# display_prog.net
KiCad netlist of a schematic drawn in EAGLE
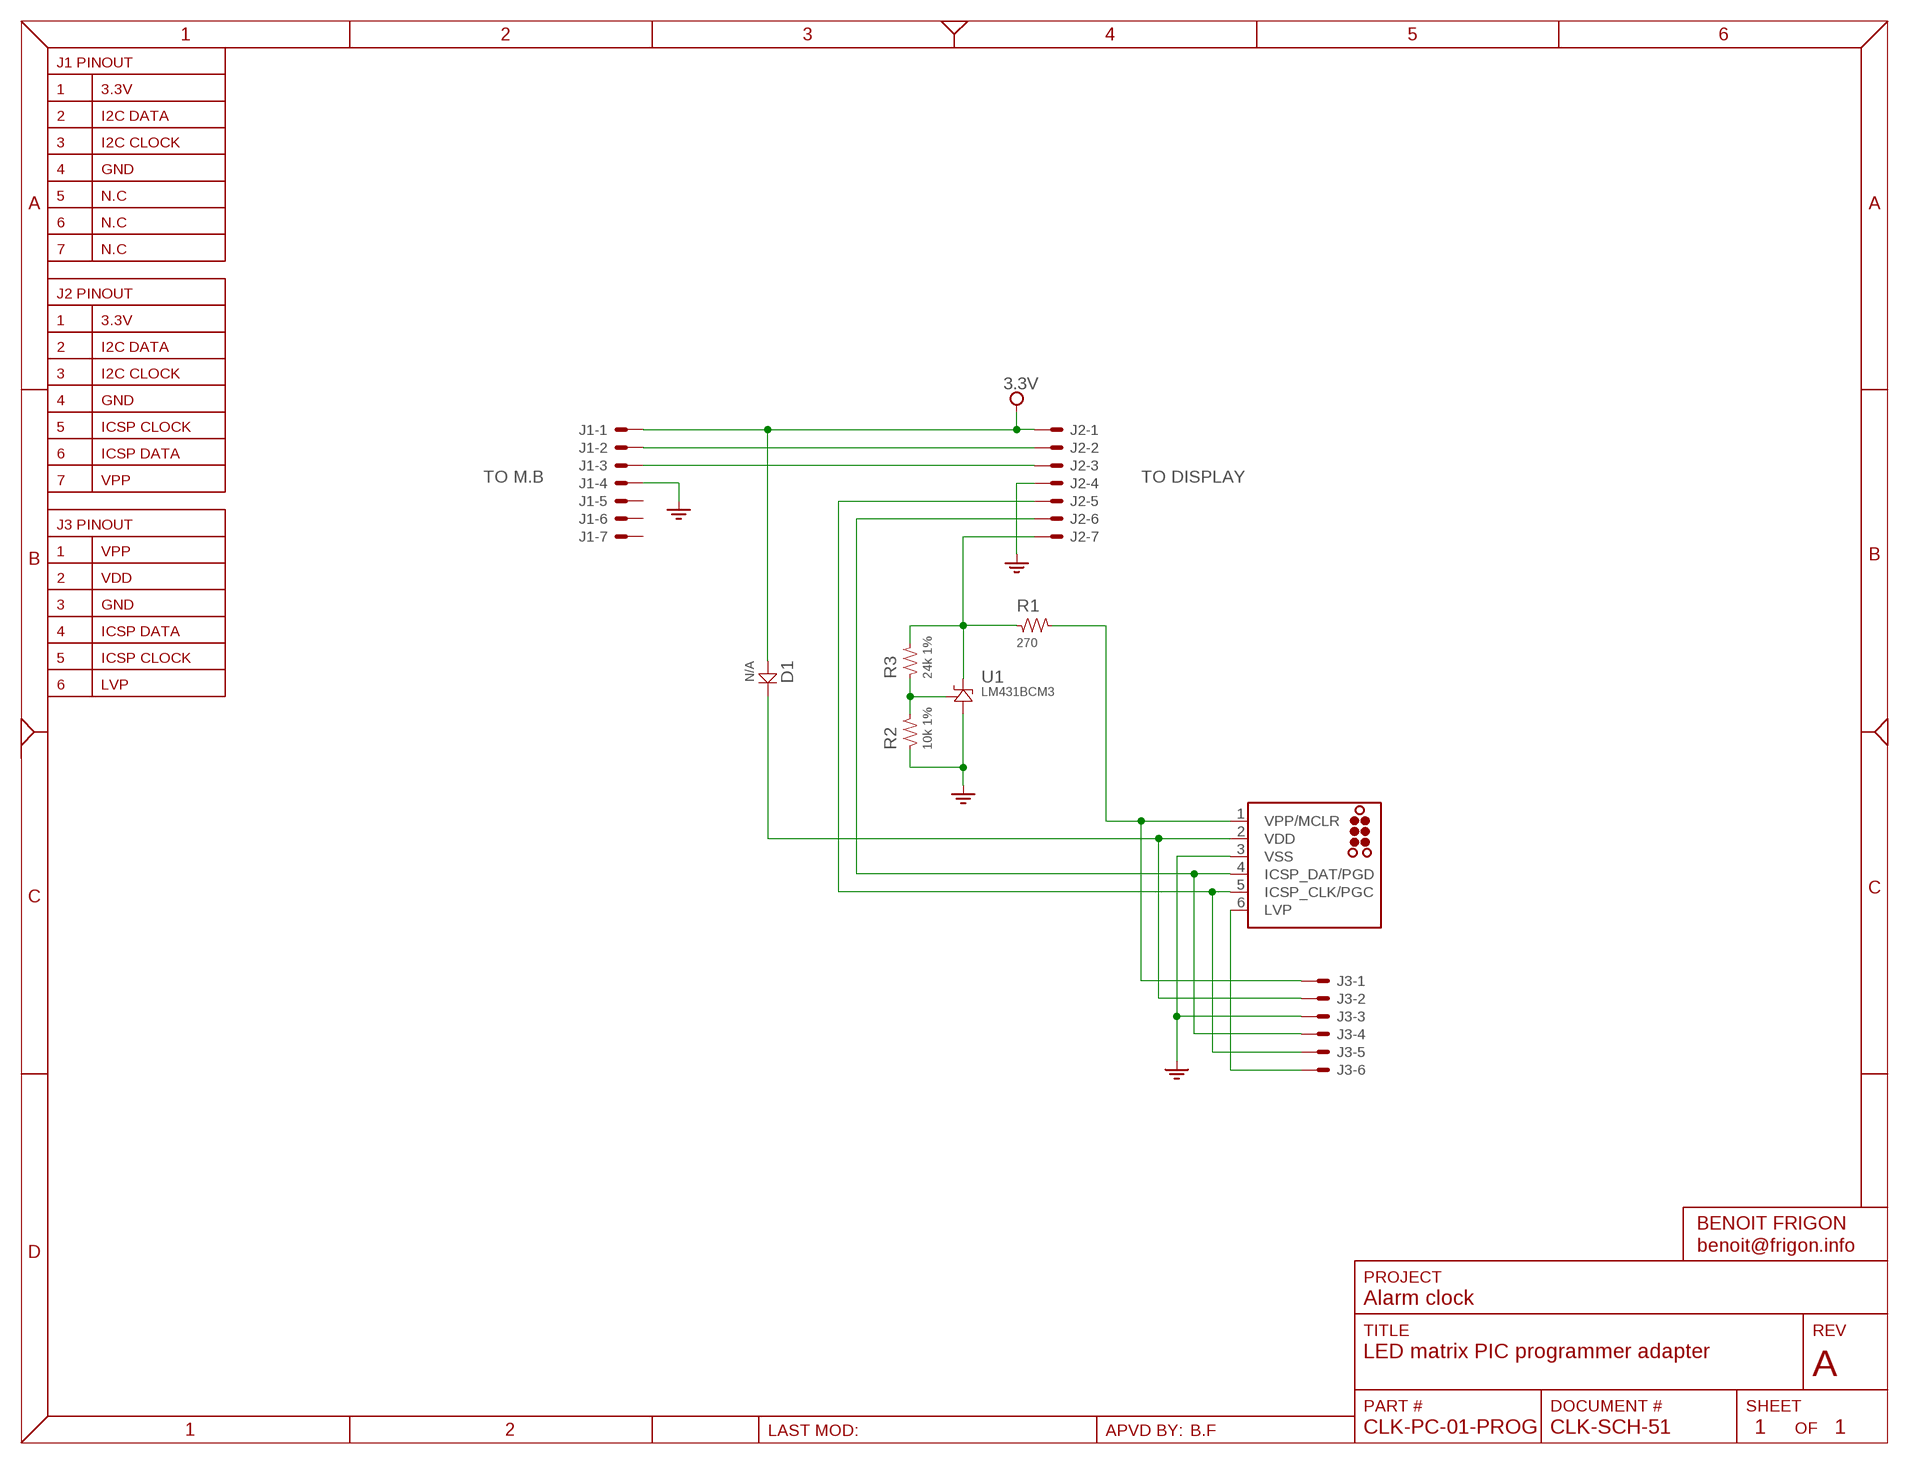
[diagram p0: schematic, sheet 1]

(export (version "E")
  (design (tool "Eeschema 10.0.6"))
  (components
    (comp (ref "D1")
      (value "N/A")
      (footprint "eagle-import:DIODE_0603")
      (libsource (lib "eagle-import") (part "DIODE-0603"))
    )
    (comp (ref "J1")
      (value "SNG-2MM-HEADER-07-V")
      (footprint "eagle-import:DF3X-7P-2DSA")
      (description "{DESCRIPTION} - SMT Vertical")
      (fields
        (field (name "MFG") "Hirose Electronic")
        (field (name "MFG_1") "Hirose Electronic")
        (field (name "SKU") "DF3X-7P-2DSA")
      )
      (libsource (lib "eagle-import") (part "SNG-2MM-HEADER-07-V"))
    )
    (comp (ref "J2")
      (value "SNG-2MM-HEADER-07-V")
      (footprint "eagle-import:DF3X-7P-2DSA")
      (fields (field (name "MFG") "Hirose Electronic"))
      (libsource (lib "eagle-import") (part "SNG-2MM-HEADER-07-V"))
    )
    (comp (ref "J3")
      (value "SNG-100-HEADER-06-FL-V")
      (footprint "eagle-import:22-23-2061")
      (fields (field (name "MFG") "Molex"))
      (libsource (lib "eagle-import") (part "SNG-100-HEADER-06-FL-V"))
    )
    (comp (ref "J4")
      (value "TC2030-MCP")
      (footprint "eagle-import:TC2030-MCP")
      (fields (field (name "MFG") "Tag-Connect"))
      (libsource (lib "eagle-import") (part "TC2030-MCP"))
    )
    (comp (ref "R1")
      (value "270")
      (footprint "eagle-import:SMD_0603")
      (libsource (lib "eagle-import") (part "RES-0603"))
    )
    (comp (ref "R2")
      (value "10k 1%")
      (footprint "eagle-import:SMD_0603")
      (libsource (lib "eagle-import") (part "RES-0603"))
    )
    (comp (ref "R3")
      (value "24k 1%")
      (footprint "eagle-import:SMD_0603")
      (libsource (lib "eagle-import") (part "RES-0603"))
    )
    (comp (ref "U1")
      (value "LM431BCM3")
      (footprint "eagle-import:SOT23")
      (fields (field (name "MFG") "Texas Instruments"))
      (libsource (lib "eagle-import") (part "LM431?M3BC"))
    )
  )
  (nets
    (net (code "1") (name "3.3V") (class "Default")
      (node (ref "D1") (pin "A") (pinfunction "A_A") (pintype "passive"))
      (node (ref "J1") (pin "1") (pinfunction "S_1") (pintype "bidirectional"))
      (node (ref "J2") (pin "1") (pinfunction "S_1") (pintype "bidirectional"))
    )
    (net (code "2") (name "GND") (class "Default")
      (node (ref "J1") (pin "4") (pinfunction "S_4") (pintype "bidirectional"))
      (node (ref "J2") (pin "4") (pinfunction "S_4") (pintype "bidirectional"))
      (node (ref "J3") (pin "3") (pinfunction "S_3") (pintype "bidirectional"))
      (node (ref "J4") (pin "3") (pinfunction "VSS_3") (pintype "power_in"))
      (node (ref "R2") (pin "1") (pinfunction "1_1") (pintype "passive"))
      (node (ref "U1") (pin "3") (pinfunction "A_3") (pintype "passive"))
    )
    (net (code "3") (name "Net-(J1B-S)") (class "Default")
      (node (ref "J1") (pin "2") (pinfunction "S_2") (pintype "bidirectional"))
      (node (ref "J2") (pin "2") (pinfunction "S_2") (pintype "bidirectional"))
    )
    (net (code "4") (name "Net-(J1C-S)") (class "Default")
      (node (ref "J1") (pin "3") (pinfunction "S_3") (pintype "bidirectional"))
      (node (ref "J2") (pin "3") (pinfunction "S_3") (pintype "bidirectional"))
    )
    (net (code "5") (name "Net-(J2E-S)") (class "Default")
      (node (ref "J2") (pin "5") (pinfunction "S_5") (pintype "bidirectional"))
      (node (ref "J3") (pin "5") (pinfunction "S_5") (pintype "bidirectional"))
      (node (ref "J4") (pin "5") (pinfunction "ICSP_CLK/PGC_5") (pintype "output"))
    )
    (net (code "6") (name "Net-(J2F-S)") (class "Default")
      (node (ref "J2") (pin "6") (pinfunction "S_6") (pintype "bidirectional"))
      (node (ref "J3") (pin "4") (pinfunction "S_4") (pintype "bidirectional"))
      (node (ref "J4") (pin "4") (pinfunction "ICSP_DAT/PGD_4") (pintype "bidirectional"))
    )
    (net (code "7") (name "Net-(J2G-S)") (class "Default")
      (node (ref "J2") (pin "7") (pinfunction "S_7") (pintype "bidirectional"))
      (node (ref "R1") (pin "1") (pinfunction "1_1") (pintype "passive"))
      (node (ref "R3") (pin "2") (pinfunction "2_2") (pintype "passive"))
      (node (ref "U1") (pin "1") (pinfunction "K_1") (pintype "passive"))
    )
    (net (code "8") (name "Net-(J3A-S)") (class "Default")
      (node (ref "J3") (pin "1") (pinfunction "S_1") (pintype "bidirectional"))
      (node (ref "J4") (pin "1") (pinfunction "VPP/MCLR_1") (pintype "passive"))
      (node (ref "R1") (pin "2") (pinfunction "2_2") (pintype "passive"))
    )
    (net (code "9") (name "Net-(J3B-S)") (class "Default")
      (node (ref "D1") (pin "K") (pinfunction "K_K") (pintype "passive"))
      (node (ref "J3") (pin "2") (pinfunction "S_2") (pintype "bidirectional"))
      (node (ref "J4") (pin "2") (pinfunction "VDD_2") (pintype "power_in"))
    )
    (net (code "10") (name "Net-(J3F-S)") (class "Default")
      (node (ref "J3") (pin "6") (pinfunction "S_6") (pintype "bidirectional"))
      (node (ref "J4") (pin "6") (pinfunction "LVP_6") (pintype "bidirectional"))
    )
    (net (code "11") (name "Net-(U1-ADJ)") (class "Default")
      (node (ref "R2") (pin "2") (pinfunction "2_2") (pintype "passive"))
      (node (ref "R3") (pin "1") (pinfunction "1_1") (pintype "passive"))
      (node (ref "U1") (pin "2") (pinfunction "ADJ_2") (pintype "passive"))
    )
    (net (code "12") (name "unconnected-(J1E-S-Pad5)") (class "Default")
      (node (ref "J1") (pin "5") (pinfunction "S_5") (pintype "bidirectional"))
    )
    (net (code "13") (name "unconnected-(J1F-S-Pad6)") (class "Default")
      (node (ref "J1") (pin "6") (pinfunction "S_6") (pintype "bidirectional"))
    )
    (net (code "14") (name "unconnected-(J1G-S-Pad7)") (class "Default")
      (node (ref "J1") (pin "7") (pinfunction "S_7") (pintype "bidirectional"))
    )
  )
)
